# main.net
KiCad netlist of a schematic drawn in EAGLE
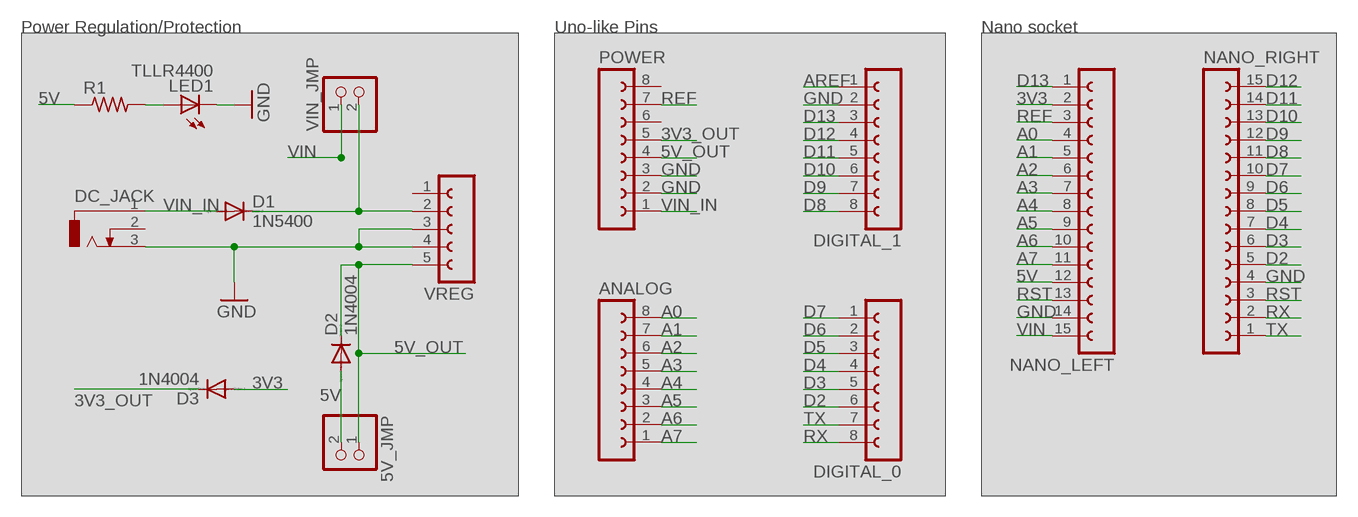
[diagram p0: schematic, sheet 1]

(export (version "E")
  (design (tool "Eeschema 10.0.6"))
  (components
    (comp (ref "5V_JMP")
      (value "PINHD-1X2")
      (footprint "eagle-import:1X02")
      (libsource (lib "eagle-import") (part "PINHD-1X2"))
    )
    (comp (ref "ANALOG")
      (value "FE08-1")
      (footprint "eagle-import:FE08")
      (libsource (lib "eagle-import") (part "FE08-1"))
    )
    (comp (ref "D1")
      (value "1N5400")
      (footprint "eagle-import:DO201-15")
      (libsource (lib "eagle-import") (part "1N5400"))
    )
    (comp (ref "D2")
      (value "1N4004")
      (footprint "eagle-import:DO41-10")
      (libsource (lib "eagle-import") (part "1N4004"))
    )
    (comp (ref "D3")
      (value "1N4004")
      (footprint "eagle-import:DO41-10")
      (libsource (lib "eagle-import") (part "1N4004"))
    )
    (comp (ref "DC_JACK")
      (value "DCJ0303")
      (footprint "eagle-import:DCJ0303")
      (libsource (lib "eagle-import") (part "DCJ0303"))
    )
    (comp (ref "DIGITAL_0")
      (value "FE08-1")
      (footprint "eagle-import:FE08")
      (libsource (lib "eagle-import") (part "FE08-1"))
    )
    (comp (ref "DIGITAL_1")
      (value "FE08-1")
      (footprint "eagle-import:FE08")
      (libsource (lib "eagle-import") (part "FE08-1"))
    )
    (comp (ref "LED1")
      (value "TLLR4400")
      (footprint "eagle-import:LED3MM")
      (fields (field (name "MF") "VISHAY SEMICONDUCTOR"))
      (libsource (lib "eagle-import") (part "TLLR4400"))
    )
    (comp (ref "NANO_LEFT")
      (value "FE15-1")
      (footprint "eagle-import:FE15")
      (libsource (lib "eagle-import") (part "FE15-1"))
    )
    (comp (ref "NANO_RIGHT")
      (value "FE15-1")
      (footprint "eagle-import:FE15")
      (libsource (lib "eagle-import") (part "FE15-1"))
    )
    (comp (ref "POWER")
      (value "FE08-1")
      (footprint "eagle-import:FE08")
      (libsource (lib "eagle-import") (part "FE08-1"))
    )
    (comp (ref "R1")
      (value "R-US_0207/10")
      (footprint "eagle-import:0207_10")
      (libsource (lib "eagle-import") (part "R-US_0207/10"))
    )
    (comp (ref "VIN_JMP")
      (value "PINHD-1X2")
      (footprint "eagle-import:1X02")
      (libsource (lib "eagle-import") (part "PINHD-1X2"))
    )
    (comp (ref "VREG")
      (value "FE05-1")
      (footprint "eagle-import:FE05-1")
      (libsource (lib "eagle-import") (part "FE05-1"))
    )
  )
  (nets
    (net (code "1") (name "/3V3") (class "Default")
      (node (ref "D3") (pin "A") (pinfunction "A_A") (pintype "passive"))
      (node (ref "NANO_LEFT") (pin "2") (pinfunction "2_2") (pintype "passive"))
    )
    (net (code "2") (name "/3V3_OUT") (class "Default")
      (node (ref "D3") (pin "C") (pinfunction "C_C") (pintype "passive"))
      (node (ref "POWER") (pin "5") (pinfunction "5_5") (pintype "passive"))
    )
    (net (code "3") (name "/5V") (class "Default")
      (node (ref "5V_JMP") (pin "2") (pinfunction "2_2") (pintype "passive"))
      (node (ref "D2") (pin "A") (pinfunction "A_A") (pintype "passive"))
      (node (ref "NANO_LEFT") (pin "12") (pinfunction "12_12") (pintype "passive"))
      (node (ref "R1") (pin "1") (pinfunction "1_1") (pintype "passive"))
    )
    (net (code "4") (name "/5V_OUT") (class "Default")
      (node (ref "5V_JMP") (pin "1") (pinfunction "1_1") (pintype "passive"))
      (node (ref "D2") (pin "C") (pinfunction "C_C") (pintype "passive"))
      (node (ref "POWER") (pin "4") (pinfunction "4_4") (pintype "passive"))
      (node (ref "VREG") (pin "5") (pinfunction "5_5") (pintype "passive"))
    )
    (net (code "5") (name "/A0") (class "Default")
      (node (ref "ANALOG") (pin "8") (pinfunction "8_8") (pintype "passive"))
      (node (ref "NANO_LEFT") (pin "4") (pinfunction "4_4") (pintype "passive"))
    )
    (net (code "6") (name "/A1") (class "Default")
      (node (ref "ANALOG") (pin "7") (pinfunction "7_7") (pintype "passive"))
      (node (ref "NANO_LEFT") (pin "5") (pinfunction "5_5") (pintype "passive"))
    )
    (net (code "7") (name "/A2") (class "Default")
      (node (ref "ANALOG") (pin "6") (pinfunction "6_6") (pintype "passive"))
      (node (ref "NANO_LEFT") (pin "6") (pinfunction "6_6") (pintype "passive"))
    )
    (net (code "8") (name "/A3") (class "Default")
      (node (ref "ANALOG") (pin "5") (pinfunction "5_5") (pintype "passive"))
      (node (ref "NANO_LEFT") (pin "7") (pinfunction "7_7") (pintype "passive"))
    )
    (net (code "9") (name "/A4") (class "Default")
      (node (ref "ANALOG") (pin "4") (pinfunction "4_4") (pintype "passive"))
      (node (ref "NANO_LEFT") (pin "8") (pinfunction "8_8") (pintype "passive"))
    )
    (net (code "10") (name "/A5") (class "Default")
      (node (ref "ANALOG") (pin "3") (pinfunction "3_3") (pintype "passive"))
      (node (ref "NANO_LEFT") (pin "9") (pinfunction "9_9") (pintype "passive"))
    )
    (net (code "11") (name "/A6") (class "Default")
      (node (ref "ANALOG") (pin "2") (pinfunction "2_2") (pintype "passive"))
      (node (ref "NANO_LEFT") (pin "10") (pinfunction "10_10") (pintype "passive"))
    )
    (net (code "12") (name "/A7") (class "Default")
      (node (ref "ANALOG") (pin "1") (pinfunction "1_1") (pintype "passive"))
      (node (ref "NANO_LEFT") (pin "11") (pinfunction "11_11") (pintype "passive"))
    )
    (net (code "13") (name "/AREF") (class "Default")
      (node (ref "DIGITAL_1") (pin "1") (pinfunction "1_1") (pintype "passive"))
    )
    (net (code "14") (name "/D2") (class "Default")
      (node (ref "DIGITAL_0") (pin "6") (pinfunction "6_6") (pintype "passive"))
      (node (ref "NANO_RIGHT") (pin "5") (pinfunction "5_5") (pintype "passive"))
    )
    (net (code "15") (name "/D3") (class "Default")
      (node (ref "DIGITAL_0") (pin "5") (pinfunction "5_5") (pintype "passive"))
      (node (ref "NANO_RIGHT") (pin "6") (pinfunction "6_6") (pintype "passive"))
    )
    (net (code "16") (name "/D4") (class "Default")
      (node (ref "DIGITAL_0") (pin "4") (pinfunction "4_4") (pintype "passive"))
      (node (ref "NANO_RIGHT") (pin "7") (pinfunction "7_7") (pintype "passive"))
    )
    (net (code "17") (name "/D5") (class "Default")
      (node (ref "DIGITAL_0") (pin "3") (pinfunction "3_3") (pintype "passive"))
      (node (ref "NANO_RIGHT") (pin "8") (pinfunction "8_8") (pintype "passive"))
    )
    (net (code "18") (name "/D6") (class "Default")
      (node (ref "DIGITAL_0") (pin "2") (pinfunction "2_2") (pintype "passive"))
      (node (ref "NANO_RIGHT") (pin "9") (pinfunction "9_9") (pintype "passive"))
    )
    (net (code "19") (name "/D7") (class "Default")
      (node (ref "DIGITAL_0") (pin "1") (pinfunction "1_1") (pintype "passive"))
      (node (ref "NANO_RIGHT") (pin "10") (pinfunction "10_10") (pintype "passive"))
    )
    (net (code "20") (name "/D8") (class "Default")
      (node (ref "DIGITAL_1") (pin "8") (pinfunction "8_8") (pintype "passive"))
      (node (ref "NANO_RIGHT") (pin "11") (pinfunction "11_11") (pintype "passive"))
    )
    (net (code "21") (name "/D9") (class "Default")
      (node (ref "DIGITAL_1") (pin "7") (pinfunction "7_7") (pintype "passive"))
      (node (ref "NANO_RIGHT") (pin "12") (pinfunction "12_12") (pintype "passive"))
    )
    (net (code "22") (name "/D10") (class "Default")
      (node (ref "DIGITAL_1") (pin "6") (pinfunction "6_6") (pintype "passive"))
      (node (ref "NANO_RIGHT") (pin "13") (pinfunction "13_13") (pintype "passive"))
    )
    (net (code "23") (name "/D11") (class "Default")
      (node (ref "DIGITAL_1") (pin "5") (pinfunction "5_5") (pintype "passive"))
      (node (ref "NANO_RIGHT") (pin "14") (pinfunction "14_14") (pintype "passive"))
    )
    (net (code "24") (name "/D12") (class "Default")
      (node (ref "DIGITAL_1") (pin "4") (pinfunction "4_4") (pintype "passive"))
      (node (ref "NANO_RIGHT") (pin "15") (pinfunction "15_15") (pintype "passive"))
    )
    (net (code "25") (name "/D13") (class "Default")
      (node (ref "DIGITAL_1") (pin "3") (pinfunction "3_3") (pintype "passive"))
      (node (ref "NANO_LEFT") (pin "1") (pinfunction "1_1") (pintype "passive"))
    )
    (net (code "26") (name "/REF") (class "Default")
      (node (ref "NANO_LEFT") (pin "3") (pinfunction "3_3") (pintype "passive"))
      (node (ref "POWER") (pin "7") (pinfunction "7_7") (pintype "passive"))
    )
    (net (code "27") (name "/RST") (class "Default")
      (node (ref "NANO_LEFT") (pin "13") (pinfunction "13_13") (pintype "passive"))
      (node (ref "NANO_RIGHT") (pin "3") (pinfunction "3_3") (pintype "passive"))
    )
    (net (code "28") (name "/RX") (class "Default")
      (node (ref "DIGITAL_0") (pin "8") (pinfunction "8_8") (pintype "passive"))
      (node (ref "NANO_RIGHT") (pin "2") (pinfunction "2_2") (pintype "passive"))
    )
    (net (code "29") (name "/TX") (class "Default")
      (node (ref "DIGITAL_0") (pin "7") (pinfunction "7_7") (pintype "passive"))
      (node (ref "NANO_RIGHT") (pin "1") (pinfunction "1_1") (pintype "passive"))
    )
    (net (code "30") (name "/VIN") (class "Default")
      (node (ref "NANO_LEFT") (pin "15") (pinfunction "15_15") (pintype "passive"))
      (node (ref "VIN_JMP") (pin "1") (pinfunction "1_1") (pintype "passive"))
    )
    (net (code "31") (name "/VIN_IN") (class "Default")
      (node (ref "D1") (pin "A") (pinfunction "A_A") (pintype "passive"))
      (node (ref "DC_JACK") (pin "1") (pinfunction "1_1") (pintype "passive"))
      (node (ref "POWER") (pin "1") (pinfunction "1_1") (pintype "passive"))
    )
    (net (code "32") (name "GND") (class "Default")
      (node (ref "DC_JACK") (pin "3") (pinfunction "3_3") (pintype "passive"))
      (node (ref "DIGITAL_1") (pin "2") (pinfunction "2_2") (pintype "passive"))
      (node (ref "LED1") (pin "K") (pinfunction "C_K") (pintype "passive"))
      (node (ref "NANO_LEFT") (pin "14") (pinfunction "14_14") (pintype "passive"))
      (node (ref "NANO_RIGHT") (pin "4") (pinfunction "4_4") (pintype "passive"))
      (node (ref "POWER") (pin "2") (pinfunction "2_2") (pintype "passive"))
      (node (ref "POWER") (pin "3") (pinfunction "3_3") (pintype "passive"))
      (node (ref "VREG") (pin "3") (pinfunction "3_3") (pintype "passive"))
      (node (ref "VREG") (pin "4") (pinfunction "4_4") (pintype "passive"))
    )
    (net (code "33") (name "Net-(D1-PadC)") (class "Default")
      (node (ref "D1") (pin "C") (pinfunction "C_C") (pintype "passive"))
      (node (ref "VIN_JMP") (pin "2") (pinfunction "2_2") (pintype "passive"))
      (node (ref "VREG") (pin "2") (pinfunction "2_2") (pintype "passive"))
    )
    (net (code "34") (name "Net-(LED1-PadA)") (class "Default")
      (node (ref "LED1") (pin "A") (pinfunction "A_A") (pintype "passive"))
      (node (ref "R1") (pin "2") (pinfunction "2_2") (pintype "passive"))
    )
    (net (code "35") (name "unconnected-(DC_JACK-Pad2)") (class "Default")
      (node (ref "DC_JACK") (pin "2") (pinfunction "2_2") (pintype "passive"))
    )
    (net (code "36") (name "unconnected-(POWER-Pad6)") (class "Default")
      (node (ref "POWER") (pin "6") (pinfunction "6_6") (pintype "passive"))
    )
    (net (code "37") (name "unconnected-(POWER-Pad8)") (class "Default")
      (node (ref "POWER") (pin "8") (pinfunction "8_8") (pintype "passive"))
    )
    (net (code "38") (name "unconnected-(VREG-Pad1)") (class "Default")
      (node (ref "VREG") (pin "1") (pinfunction "1_1") (pintype "passive"))
    )
  )
)
